# 3__SO-DIMM.net
KiCad netlist of a schematic drawn in Altium Designer
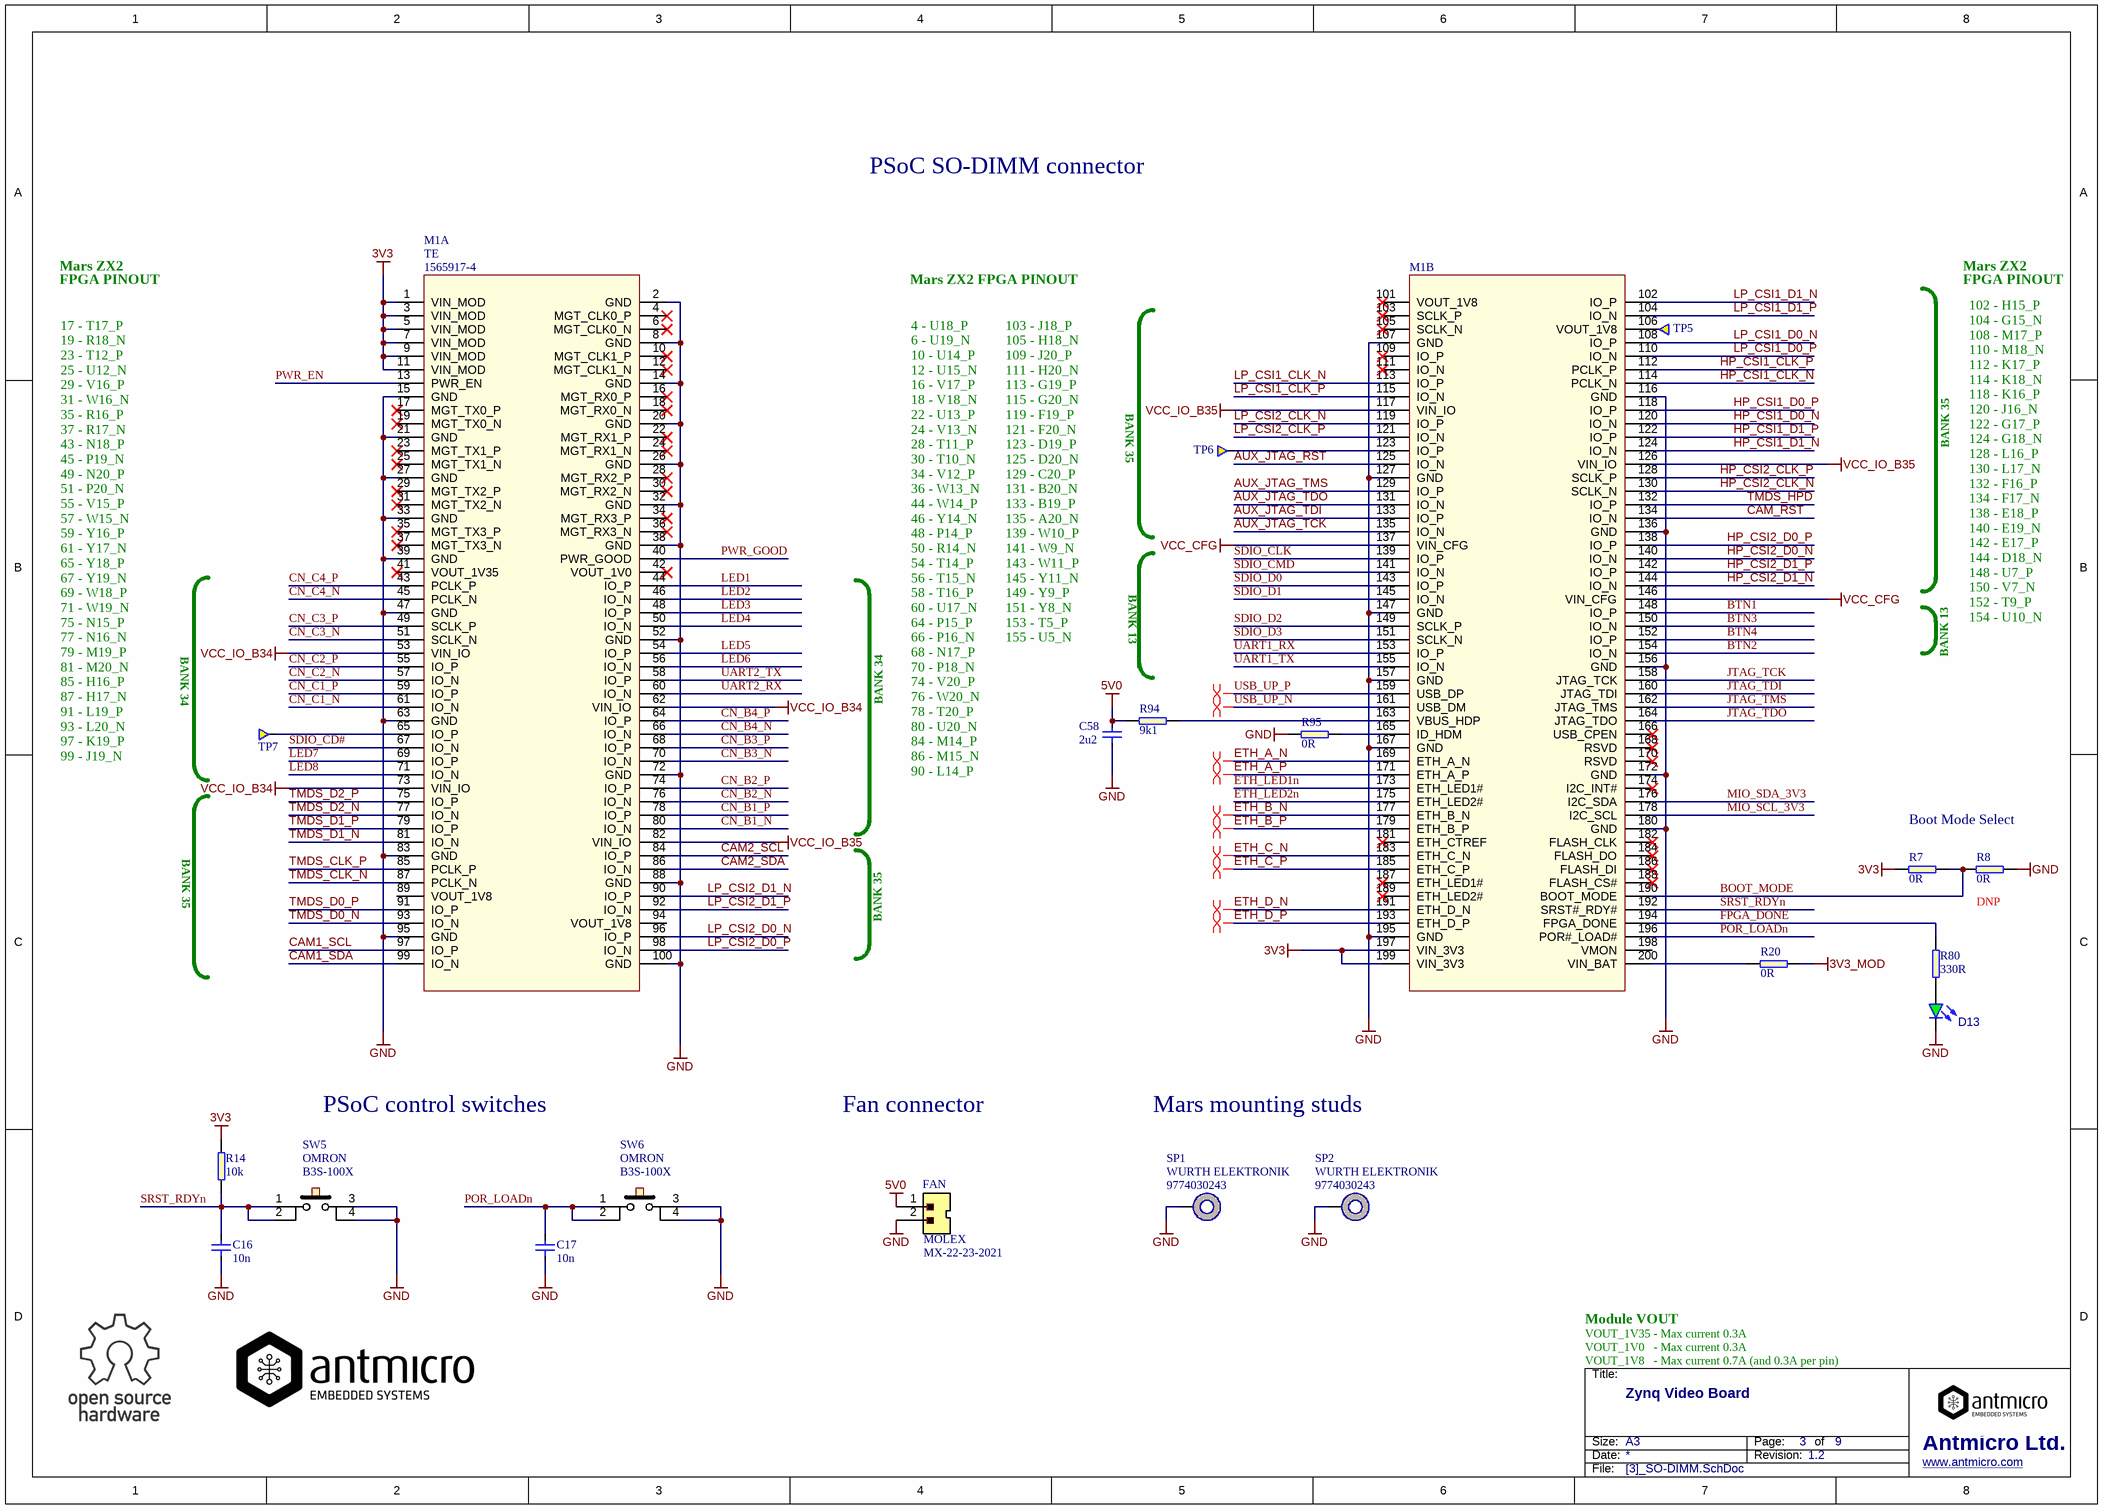
[diagram p0: [3]_SO-DIMM.SchDoc]

(export (version "E")
  (design (tool "Eeschema 10.0.6"))
  (components
    (comp (ref "C16")
      (value "10n")
      (footprint "0402")
      (description "MLCC SMT Capacitor 10nF 0402")
      (fields (field (name "PART NUMBER") "C_10n_0402") (field (name "VOLTAGE") "50V"))
      (libsource (lib "Zynq-Video-Board-Rev-1.2") (part "C_10n_0402"))
    )
    (comp (ref "C17")
      (value "10n")
      (footprint "0402")
      (description "MLCC SMT Capacitor 10nF 0402")
      (fields (field (name "PART NUMBER") "C_10n_0402") (field (name "VOLTAGE") "50V"))
      (libsource (lib "Zynq-Video-Board-Rev-1.2") (part "C_10n_0402"))
    )
    (comp (ref "C58")
      (value "2u2")
      (footprint "0603")
      (description "MLCC SMT Capacitor 2u2F 0603")
      (fields (field (name "PART NUMBER") "C_2u2_0603") (field (name "VOLTAGE") "35V"))
      (libsource (lib "Zynq-Video-Board-Rev-1.2") (part "C_2u2_0603"))
    )
    (comp (ref "D13")
      (value "KPT-1608SGC")
      (footprint "LED0603")
      (description "LED Green 0603 case")
      (fields (field (name "PART NUMBER") "LED_G") (field (name "MANUFACTURER") "KINGBRIGHT"))
      (libsource (lib "Zynq-Video-Board-Rev-1.2") (part "LED"))
    )
    (comp (ref "FAN")
      (value "MX-22-23-2021")
      (footprint "molex_2223-2021")
      (description "Pinhead connector with key")
      (fields (field (name "PART NUMBER") "molex_2223-2021") (field (name "MANUFACTURER") "MOLEX"))
      (libsource (lib "Zynq-Video-Board-Rev-1.2") (part "molex_2223-2021"))
    )
    (comp (ref "M1")
      (value "1565917-4")
      (footprint "TE_1565917-4")
      (description "SODIMM Connector 200_1V8")
      (fields (field (name "PART NUMBER") "Mars ZX2") (field (name "MANUFACTURER") "TE"))
      (libsource (lib "Zynq-Video-Board-Rev-1.2") (part "Mars ZX2"))
    )
    (comp (ref "R7")
      (value "0R")
      (footprint "0402")
      (description "SMT Resistor 0R 0402")
      (fields (field (name "PART NUMBER") "R_0R_0402") (field (name "MANUFACTURER") "MULTICOMP"))
      (libsource (lib "Zynq-Video-Board-Rev-1.2") (part "R_0R_0402"))
    )
    (comp (ref "R8")
      (value "0R")
      (footprint "0402")
      (description "SMT Resistor 0R 0402")
      (fields (field (name "PART NUMBER") "R_0R_0402") (field (name "MANUFACTURER") "MULTICOMP"))
      (libsource (lib "Zynq-Video-Board-Rev-1.2") (part "R_0R_0402"))
    )
    (comp (ref "R14")
      (value "10k")
      (footprint "0402")
      (description "SMT Resistor 10k 0402")
      (fields (field (name "PART NUMBER") "R_10k_0402") (field (name "TOLERANCE") "1%"))
      (libsource (lib "Zynq-Video-Board-Rev-1.2") (part "R_10k_0402"))
    )
    (comp (ref "R20")
      (value "0R")
      (footprint "0402")
      (description "SMT Resistor 0R 0402")
      (fields (field (name "PART NUMBER") "R_0R_0402") (field (name "MANUFACTURER") "MULTICOMP"))
      (libsource (lib "Zynq-Video-Board-Rev-1.2") (part "R_0R_0402"))
    )
    (comp (ref "R80")
      (value "330R")
      (footprint "0402")
      (description "SMT Resistor 330R 0402")
      (fields (field (name "PART NUMBER") "R_330R_0402") (field (name "TOLERANCE") "1%"))
      (libsource (lib "Zynq-Video-Board-Rev-1.2") (part "R_330R_0402"))
    )
    (comp (ref "R94")
      (value "9k1")
      (footprint "0402")
      (description "SMT Resistor 9k1 0402")
      (fields (field (name "PART NUMBER") "R_9k1_0402") (field (name "TOLERANCE") "1%"))
      (libsource (lib "Zynq-Video-Board-Rev-1.2") (part "R_9k1_0402"))
    )
    (comp (ref "R95")
      (value "0R")
      (footprint "0402")
      (description "SMT Resistor 0R 0402")
      (fields (field (name "PART NUMBER") "R_0R_0402") (field (name "MANUFACTURER") "MULTICOMP"))
      (libsource (lib "Zynq-Video-Board-Rev-1.2") (part "R_0R_0402"))
    )
    (comp (ref "SP1")
      (value "9774030243")
      (footprint "M2-3mm")
      (description "M2x3")
      (fields (field (name "PART NUMBER") "WE_9774030243") (field (name "MANUFACTURER") "WURTH ELEKTRONIK"))
      (libsource (lib "Zynq-Video-Board-Rev-1.2") (part "SPACER"))
    )
    (comp (ref "SP2")
      (value "9774030243")
      (footprint "M2-3mm")
      (description "M2x3")
      (fields (field (name "PART NUMBER") "WE_9774030243") (field (name "MANUFACTURER") "WURTH ELEKTRONIK"))
      (libsource (lib "Zynq-Video-Board-Rev-1.2") (part "SPACER"))
    )
    (comp (ref "SW5")
      (value "B3S-100X")
      (footprint "B3S-100X")
      (description "Tactile switch")
      (fields (field (name "PART NUMBER") "B3S-1002") (field (name "MANUFACTURER") "OMRON"))
      (libsource (lib "Zynq-Video-Board-Rev-1.2") (part "TACTILE_SWITCH"))
    )
    (comp (ref "SW6")
      (value "B3S-100X")
      (footprint "B3S-100X")
      (description "Tactile switch")
      (fields (field (name "PART NUMBER") "B3S-1002") (field (name "MANUFACTURER") "OMRON"))
      (libsource (lib "Zynq-Video-Board-Rev-1.2") (part "TACTILE_SWITCH"))
    )
    (comp (ref "TP5")
      (value "Testpad")
      (footprint "TP-R-2")
      (description "Testpad, round, 2mm")
      (fields (field (name "PART NUMBER") "TP-R-2"))
      (libsource (lib "Zynq-Video-Board-Rev-1.2") (part "Testpad"))
    )
    (comp (ref "TP6")
      (value "Testpad")
      (footprint "TP-R-2")
      (description "Testpad, round, 2mm")
      (fields (field (name "PART NUMBER") "TP-R-2"))
      (libsource (lib "Zynq-Video-Board-Rev-1.2") (part "Testpad"))
    )
    (comp (ref "TP7")
      (value "Testpad")
      (footprint "TP-R-2")
      (description "Testpad, round, 2mm")
      (fields (field (name "PART NUMBER") "TP-R-2"))
      (libsource (lib "Zynq-Video-Board-Rev-1.2") (part "Testpad"))
    )
  )
  (nets
    (net (code "1") (name "/AUX_JTAG_RST") (class "Default")
      (node (ref "M1") (pin "125") (pinfunction "IO_N_125") (pintype "passive"))
    )
    (net (code "2") (name "/AUX_JTAG_TCK") (class "Default")
      (node (ref "M1") (pin "135") (pinfunction "IO_N_135") (pintype "passive"))
    )
    (net (code "3") (name "/AUX_JTAG_TDI") (class "Default")
      (node (ref "M1") (pin "133") (pinfunction "IO_P_133") (pintype "passive"))
    )
    (net (code "4") (name "/AUX_JTAG_TDO") (class "Default")
      (node (ref "M1") (pin "131") (pinfunction "IO_N_131") (pintype "passive"))
    )
    (net (code "5") (name "/AUX_JTAG_TMS") (class "Default")
      (node (ref "M1") (pin "129") (pinfunction "IO_P_129") (pintype "passive"))
    )
    (net (code "6") (name "/BOOT_MODE") (class "Default")
      (node (ref "M1") (pin "190") (pinfunction "BOOT_MODE_190") (pintype "passive"))
      (node (ref "R7") (pin "2") (pintype "passive"))
      (node (ref "R8") (pin "1") (pintype "passive"))
    )
    (net (code "7") (name "/BTN1") (class "Default")
      (node (ref "M1") (pin "148") (pinfunction "IO_P_148") (pintype "passive"))
    )
    (net (code "8") (name "/BTN2") (class "Default")
      (node (ref "M1") (pin "154") (pinfunction "IO_N_154") (pintype "passive"))
    )
    (net (code "9") (name "/BTN3") (class "Default")
      (node (ref "M1") (pin "150") (pinfunction "IO_N_150") (pintype "passive"))
    )
    (net (code "10") (name "/BTN4") (class "Default")
      (node (ref "M1") (pin "152") (pinfunction "IO_P_152") (pintype "passive"))
    )
    (net (code "11") (name "/CAM1_SCL") (class "Default")
      (node (ref "M1") (pin "97") (pinfunction "IO_P_97") (pintype "passive"))
    )
    (net (code "12") (name "/CAM1_SDA") (class "Default")
      (node (ref "M1") (pin "99") (pinfunction "IO_N_99") (pintype "passive"))
    )
    (net (code "13") (name "/CAM2_SCL") (class "Default")
      (node (ref "M1") (pin "84") (pinfunction "IO_P_84") (pintype "passive"))
    )
    (net (code "14") (name "/CAM2_SDA") (class "Default")
      (node (ref "M1") (pin "86") (pinfunction "IO_N_86") (pintype "passive"))
    )
    (net (code "15") (name "/CAM_RST") (class "Default")
      (node (ref "M1") (pin "134") (pinfunction "IO_N_134") (pintype "passive"))
    )
    (net (code "16") (name "/CN_B1_N") (class "Default")
      (node (ref "M1") (pin "80") (pinfunction "IO_N_80") (pintype "passive"))
    )
    (net (code "17") (name "/CN_B1_P") (class "Default")
      (node (ref "M1") (pin "78") (pinfunction "IO_P_78") (pintype "passive"))
    )
    (net (code "18") (name "/CN_B2_N") (class "Default")
      (node (ref "M1") (pin "76") (pinfunction "IO_N_76") (pintype "passive"))
    )
    (net (code "19") (name "/CN_B2_P") (class "Default")
      (node (ref "M1") (pin "74") (pinfunction "IO_P_74") (pintype "passive"))
    )
    (net (code "20") (name "/CN_B3_N") (class "Default")
      (node (ref "M1") (pin "70") (pinfunction "IO_N_70") (pintype "passive"))
    )
    (net (code "21") (name "/CN_B3_P") (class "Default")
      (node (ref "M1") (pin "68") (pinfunction "IO_P_68") (pintype "passive"))
    )
    (net (code "22") (name "/CN_B4_N") (class "Default")
      (node (ref "M1") (pin "66") (pinfunction "IO_N_66") (pintype "passive"))
    )
    (net (code "23") (name "/CN_B4_P") (class "Default")
      (node (ref "M1") (pin "64") (pinfunction "IO_P_64") (pintype "passive"))
    )
    (net (code "24") (name "/CN_C1_N") (class "Default")
      (node (ref "M1") (pin "61") (pinfunction "IO_N_61") (pintype "passive"))
    )
    (net (code "25") (name "/CN_C1_P") (class "Default")
      (node (ref "M1") (pin "59") (pinfunction "IO_P_59") (pintype "passive"))
    )
    (net (code "26") (name "/CN_C2_N") (class "Default")
      (node (ref "M1") (pin "57") (pinfunction "IO_N_57") (pintype "passive"))
    )
    (net (code "27") (name "/CN_C2_P") (class "Default")
      (node (ref "M1") (pin "55") (pinfunction "IO_P_55") (pintype "passive"))
    )
    (net (code "28") (name "/CN_C3_N") (class "Default")
      (node (ref "M1") (pin "51") (pinfunction "SCLK_N_51") (pintype "passive"))
    )
    (net (code "29") (name "/CN_C3_P") (class "Default")
      (node (ref "M1") (pin "49") (pinfunction "SCLK_P_49") (pintype "passive"))
    )
    (net (code "30") (name "/CN_C4_N") (class "Default")
      (node (ref "M1") (pin "45") (pinfunction "PCLK_N_45") (pintype "passive"))
    )
    (net (code "31") (name "/CN_C4_P") (class "Default")
      (node (ref "M1") (pin "43") (pinfunction "PCLK_P_43") (pintype "passive"))
    )
    (net (code "32") (name "/ETH_A_N") (class "Default")
      (node (ref "M1") (pin "169") (pinfunction "ETH_A_N_169") (pintype "passive"))
    )
    (net (code "33") (name "/ETH_A_P") (class "Default")
      (node (ref "M1") (pin "171") (pinfunction "ETH_A_P_171") (pintype "passive"))
    )
    (net (code "34") (name "/ETH_B_N") (class "Default")
      (node (ref "M1") (pin "177") (pinfunction "ETH_B_N_177") (pintype "passive"))
    )
    (net (code "35") (name "/ETH_B_P") (class "Default")
      (node (ref "M1") (pin "179") (pinfunction "ETH_B_P_179") (pintype "passive"))
    )
    (net (code "36") (name "/ETH_C_N") (class "Default")
      (node (ref "M1") (pin "183") (pinfunction "ETH_C_N_183") (pintype "passive"))
    )
    (net (code "37") (name "/ETH_C_P") (class "Default")
      (node (ref "M1") (pin "185") (pinfunction "ETH_C_P_185") (pintype "passive"))
    )
    (net (code "38") (name "/ETH_D_N") (class "Default")
      (node (ref "M1") (pin "191") (pinfunction "ETH_D_N_191") (pintype "passive"))
    )
    (net (code "39") (name "/ETH_D_P") (class "Default")
      (node (ref "M1") (pin "193") (pinfunction "ETH_D_P_193") (pintype "passive"))
    )
    (net (code "40") (name "/ETH_LED1n") (class "Default")
      (node (ref "M1") (pin "173") (pinfunction "ETH_LED1#_173") (pintype "passive"))
    )
    (net (code "41") (name "/ETH_LED2n") (class "Default")
      (node (ref "M1") (pin "175") (pinfunction "ETH_LED2#_175") (pintype "passive"))
    )
    (net (code "42") (name "/FPGA_DONE") (class "Default")
      (node (ref "M1") (pin "194") (pinfunction "FPGA_DONE_194") (pintype "passive"))
      (node (ref "R80") (pin "2") (pintype "passive"))
    )
    (net (code "43") (name "/HP_CSI1_CLK_N") (class "Default")
      (node (ref "M1") (pin "114") (pinfunction "PCLK_N_114") (pintype "passive"))
    )
    (net (code "44") (name "/HP_CSI1_CLK_P") (class "Default")
      (node (ref "M1") (pin "112") (pinfunction "PCLK_P_112") (pintype "passive"))
    )
    (net (code "45") (name "/HP_CSI1_D0_N") (class "Default")
      (node (ref "M1") (pin "120") (pinfunction "IO_N_120") (pintype "passive"))
    )
    (net (code "46") (name "/HP_CSI1_D0_P") (class "Default")
      (node (ref "M1") (pin "118") (pinfunction "IO_P_118") (pintype "passive"))
    )
    (net (code "47") (name "/HP_CSI1_D1_N") (class "Default")
      (node (ref "M1") (pin "124") (pinfunction "IO_N_124") (pintype "passive"))
    )
    (net (code "48") (name "/HP_CSI1_D1_P") (class "Default")
      (node (ref "M1") (pin "122") (pinfunction "IO_P_122") (pintype "passive"))
    )
    (net (code "49") (name "/HP_CSI2_CLK_N") (class "Default")
      (node (ref "M1") (pin "130") (pinfunction "SCLK_N_130") (pintype "passive"))
    )
    (net (code "50") (name "/HP_CSI2_CLK_P") (class "Default")
      (node (ref "M1") (pin "128") (pinfunction "SCLK_P_128") (pintype "passive"))
    )
    (net (code "51") (name "/HP_CSI2_D0_N") (class "Default")
      (node (ref "M1") (pin "140") (pinfunction "IO_N_140") (pintype "passive"))
    )
    (net (code "52") (name "/HP_CSI2_D0_P") (class "Default")
      (node (ref "M1") (pin "138") (pinfunction "IO_P_138") (pintype "passive"))
    )
    (net (code "53") (name "/HP_CSI2_D1_N") (class "Default")
      (node (ref "M1") (pin "144") (pinfunction "IO_N_144") (pintype "passive"))
    )
    (net (code "54") (name "/HP_CSI2_D1_P") (class "Default")
      (node (ref "M1") (pin "142") (pinfunction "IO_P_142") (pintype "passive"))
    )
    (net (code "55") (name "/JTAG_TCK") (class "Default")
      (node (ref "M1") (pin "158") (pinfunction "JTAG_TCK_158") (pintype "passive"))
    )
    (net (code "56") (name "/JTAG_TDI") (class "Default")
      (node (ref "M1") (pin "160") (pinfunction "JTAG_TDI_160") (pintype "passive"))
    )
    (net (code "57") (name "/JTAG_TDO") (class "Default")
      (node (ref "M1") (pin "164") (pinfunction "JTAG_TDO_164") (pintype "passive"))
    )
    (net (code "58") (name "/JTAG_TMS") (class "Default")
      (node (ref "M1") (pin "162") (pinfunction "JTAG_TMS_162") (pintype "passive"))
    )
    (net (code "59") (name "/LED1") (class "Default")
      (node (ref "M1") (pin "44") (pinfunction "IO_P_44") (pintype "passive"))
    )
    (net (code "60") (name "/LED2") (class "Default")
      (node (ref "M1") (pin "46") (pinfunction "IO_N_46") (pintype "passive"))
    )
    (net (code "61") (name "/LED3") (class "Default")
      (node (ref "M1") (pin "48") (pinfunction "IO_P_48") (pintype "passive"))
    )
    (net (code "62") (name "/LED4") (class "Default")
      (node (ref "M1") (pin "50") (pinfunction "IO_N_50") (pintype "passive"))
    )
    (net (code "63") (name "/LED5") (class "Default")
      (node (ref "M1") (pin "54") (pinfunction "IO_P_54") (pintype "passive"))
    )
    (net (code "64") (name "/LED6") (class "Default")
      (node (ref "M1") (pin "56") (pinfunction "IO_N_56") (pintype "passive"))
    )
    (net (code "65") (name "/LED7") (class "Default")
      (node (ref "M1") (pin "69") (pinfunction "IO_P_69") (pintype "passive"))
    )
    (net (code "66") (name "/LED8") (class "Default")
      (node (ref "M1") (pin "71") (pinfunction "IO_N_71") (pintype "passive"))
    )
    (net (code "67") (name "/LP_CSI1_CLK_N") (class "Default")
      (node (ref "M1") (pin "113") (pinfunction "IO_P_113") (pintype "passive"))
    )
    (net (code "68") (name "/LP_CSI1_CLK_P") (class "Default")
      (node (ref "M1") (pin "115") (pinfunction "IO_N_115") (pintype "passive"))
    )
    (net (code "69") (name "/LP_CSI1_D0_N") (class "Default")
      (node (ref "M1") (pin "108") (pinfunction "IO_P_108") (pintype "passive"))
    )
    (net (code "70") (name "/LP_CSI1_D0_P") (class "Default")
      (node (ref "M1") (pin "110") (pinfunction "IO_N_110") (pintype "passive"))
    )
    (net (code "71") (name "/LP_CSI1_D1_N") (class "Default")
      (node (ref "M1") (pin "102") (pinfunction "IO_P_102") (pintype "passive"))
    )
    (net (code "72") (name "/LP_CSI1_D1_P") (class "Default")
      (node (ref "M1") (pin "104") (pinfunction "IO_N_104") (pintype "passive"))
    )
    (net (code "73") (name "/LP_CSI2_CLK_N") (class "Default")
      (node (ref "M1") (pin "119") (pinfunction "IO_P_119") (pintype "passive"))
    )
    (net (code "74") (name "/LP_CSI2_CLK_P") (class "Default")
      (node (ref "M1") (pin "121") (pinfunction "IO_N_121") (pintype "passive"))
    )
    (net (code "75") (name "/LP_CSI2_D0_N") (class "Default")
      (node (ref "M1") (pin "96") (pinfunction "IO_P_96") (pintype "passive"))
    )
    (net (code "76") (name "/LP_CSI2_D0_P") (class "Default")
      (node (ref "M1") (pin "98") (pinfunction "IO_N_98") (pintype "passive"))
    )
    (net (code "77") (name "/LP_CSI2_D1_N") (class "Default")
      (node (ref "M1") (pin "90") (pinfunction "IO_P_90") (pintype "passive"))
    )
    (net (code "78") (name "/LP_CSI2_D1_P") (class "Default")
      (node (ref "M1") (pin "92") (pinfunction "IO_N_92") (pintype "passive"))
    )
    (net (code "79") (name "/MIO_SCL_3V3") (class "Default")
      (node (ref "M1") (pin "178") (pinfunction "I2C_SCL_178") (pintype "passive"))
    )
    (net (code "80") (name "/MIO_SDA_3V3") (class "Default")
      (node (ref "M1") (pin "176") (pinfunction "I2C_SDA_176") (pintype "passive"))
    )
    (net (code "81") (name "/POR_LOADn") (class "Default")
      (node (ref "C17") (pin "2") (pinfunction "2_2") (pintype "passive"))
      (node (ref "M1") (pin "196") (pinfunction "POR#_LOAD#_196") (pintype "passive"))
      (node (ref "SW6") (pin "1") (pinfunction "1_1") (pintype "passive"))
      (node (ref "SW6") (pin "2") (pinfunction "2_2") (pintype "passive"))
    )
    (net (code "82") (name "/PWR_EN") (class "Default")
      (node (ref "M1") (pin "13") (pinfunction "PWR_EN_13") (pintype "passive"))
    )
    (net (code "83") (name "/PWR_GOOD") (class "Default")
      (node (ref "M1") (pin "40") (pinfunction "PWR_GOOD_40") (pintype "passive"))
    )
    (net (code "84") (name "/SDIO_CD#") (class "Default")
      (node (ref "M1") (pin "67") (pinfunction "IO_N_67") (pintype "passive"))
    )
    (net (code "85") (name "/SDIO_CLK") (class "Default")
      (node (ref "M1") (pin "139") (pinfunction "IO_P_139") (pintype "passive"))
    )
    (net (code "86") (name "/SDIO_CMD") (class "Default")
      (node (ref "M1") (pin "141") (pinfunction "IO_N_141") (pintype "passive"))
    )
    (net (code "87") (name "/SDIO_D0") (class "Default")
      (node (ref "M1") (pin "143") (pinfunction "IO_P_143") (pintype "passive"))
    )
    (net (code "88") (name "/SDIO_D1") (class "Default")
      (node (ref "M1") (pin "145") (pinfunction "IO_N_145") (pintype "passive"))
    )
    (net (code "89") (name "/SDIO_D2") (class "Default")
      (node (ref "M1") (pin "149") (pinfunction "SCLK_P_149") (pintype "passive"))
    )
    (net (code "90") (name "/SDIO_D3") (class "Default")
      (node (ref "M1") (pin "151") (pinfunction "SCLK_N_151") (pintype "passive"))
    )
    (net (code "91") (name "/SRST_RDYn") (class "Default")
      (node (ref "C16") (pin "2") (pinfunction "2_2") (pintype "passive"))
      (node (ref "M1") (pin "192") (pinfunction "SRST#_RDY#_192") (pintype "passive"))
      (node (ref "R14") (pin "2") (pintype "passive"))
      (node (ref "SW5") (pin "1") (pinfunction "1_1") (pintype "passive"))
      (node (ref "SW5") (pin "2") (pinfunction "2_2") (pintype "passive"))
    )
    (net (code "92") (name "/TMDS_CLK_N") (class "Default")
      (node (ref "M1") (pin "87") (pinfunction "PCLK_N_87") (pintype "passive"))
    )
    (net (code "93") (name "/TMDS_CLK_P") (class "Default")
      (node (ref "M1") (pin "85") (pinfunction "PCLK_P_85") (pintype "passive"))
    )
    (net (code "94") (name "/TMDS_D0_N") (class "Default")
      (node (ref "M1") (pin "93") (pinfunction "IO_N_93") (pintype "passive"))
    )
    (net (code "95") (name "/TMDS_D0_P") (class "Default")
      (node (ref "M1") (pin "91") (pinfunction "IO_P_91") (pintype "passive"))
    )
    (net (code "96") (name "/TMDS_D1_N") (class "Default")
      (node (ref "M1") (pin "81") (pinfunction "IO_N_81") (pintype "passive"))
    )
    (net (code "97") (name "/TMDS_D1_P") (class "Default")
      (node (ref "M1") (pin "79") (pinfunction "IO_P_79") (pintype "passive"))
    )
    (net (code "98") (name "/TMDS_D2_N") (class "Default")
      (node (ref "M1") (pin "77") (pinfunction "IO_N_77") (pintype "passive"))
    )
    (net (code "99") (name "/TMDS_D2_P") (class "Default")
      (node (ref "M1") (pin "75") (pinfunction "IO_P_75") (pintype "passive"))
    )
    (net (code "100") (name "/TMDS_HPD") (class "Default")
      (node (ref "M1") (pin "132") (pinfunction "IO_P_132") (pintype "passive"))
    )
    (net (code "101") (name "/UART1_RX") (class "Default")
      (node (ref "M1") (pin "153") (pinfunction "IO_P_153") (pintype "passive"))
    )
    (net (code "102") (name "/UART1_TX") (class "Default")
      (node (ref "M1") (pin "155") (pinfunction "IO_N_155") (pintype "passive"))
    )
    (net (code "103") (name "/UART2_RX") (class "Default")
      (node (ref "M1") (pin "60") (pinfunction "IO_N_60") (pintype "passive"))
    )
    (net (code "104") (name "/UART2_TX") (class "Default")
      (node (ref "M1") (pin "58") (pinfunction "IO_P_58") (pintype "passive"))
    )
    (net (code "105") (name "/USB_UP_N") (class "Default")
      (node (ref "M1") (pin "161") (pinfunction "USB_DM_161") (pintype "passive"))
    )
    (net (code "106") (name "/USB_UP_P") (class "Default")
      (node (ref "M1") (pin "159") (pinfunction "USB_DP_159") (pintype "passive"))
    )
    (net (code "107") (name "3V3") (class "Default")
      (node (ref "M1") (pin "1") (pinfunction "VIN_MOD_1") (pintype "passive"))
      (node (ref "M1") (pin "11") (pinfunction "VIN_MOD_11") (pintype "passive"))
      (node (ref "M1") (pin "197") (pinfunction "VIN_3V3_197") (pintype "passive"))
      (node (ref "M1") (pin "199") (pinfunction "VIN_3V3_199") (pintype "passive"))
      (node (ref "M1") (pin "3") (pinfunction "VIN_MOD_3") (pintype "passive"))
      (node (ref "M1") (pin "5") (pinfunction "VIN_MOD_5") (pintype "passive"))
      (node (ref "M1") (pin "7") (pinfunction "VIN_MOD_7") (pintype "passive"))
      (node (ref "M1") (pin "9") (pinfunction "VIN_MOD_9") (pintype "passive"))
      (node (ref "R14") (pin "1") (pintype "passive"))
      (node (ref "R7") (pin "1") (pintype "passive"))
    )
    (net (code "108") (name "3V3_MOD") (class "Default") (node (ref "R20") (pin "2") (pintype "passive")))
    (net (code "109") (name "5V0") (class "Default")
      (node (ref "C58") (pin "2") (pinfunction "2_2") (pintype "passive"))
      (node (ref "FAN") (pin "1") (pinfunction "1_1") (pintype "passive"))
      (node (ref "R94") (pin "1") (pintype "passive"))
    )
    (net (code "110") (name "GND") (class "Default")
      (node (ref "C16") (pin "1") (pinfunction "1_1") (pintype "passive"))
      (node (ref "C17") (pin "1") (pinfunction "1_1") (pintype "passive"))
      (node (ref "C58") (pin "1") (pinfunction "1_1") (pintype "passive"))
      (node (ref "D13") (pin "K") (pinfunction "K_K") (pintype "passive"))
      (node (ref "FAN") (pin "2") (pinfunction "2_2") (pintype "passive"))
      (node (ref "M1") (pin "100") (pinfunction "GND_100") (pintype "passive"))
      (node (ref "M1") (pin "107") (pinfunction "GND_107") (pintype "passive"))
      (node (ref "M1") (pin "116") (pinfunction "GND_116") (pintype "passive"))
      (node (ref "M1") (pin "127") (pinfunction "GND_127") (pintype "passive"))
      (node (ref "M1") (pin "136") (pinfunction "GND_136") (pintype "passive"))
      (node (ref "M1") (pin "14") (pinfunction "GND_14") (pintype "passive"))
      (node (ref "M1") (pin "147") (pinfunction "GND_147") (pintype "passive"))
      (node (ref "M1") (pin "15") (pinfunction "GND_15") (pintype "passive"))
      (node (ref "M1") (pin "156") (pinfunction "GND_156") (pintype "passive"))
      (node (ref "M1") (pin "157") (pinfunction "GND_157") (pintype "passive"))
      (node (ref "M1") (pin "167") (pinfunction "GND_167") (pintype "passive"))
      (node (ref "M1") (pin "172") (pinfunction "GND_172") (pintype "passive"))
      (node (ref "M1") (pin "180") (pinfunction "GND_180") (pintype "passive"))
      (node (ref "M1") (pin "195") (pinfunction "GND_195") (pintype "passive"))
      (node (ref "M1") (pin "2") (pinfunction "GND_2") (pintype "passive"))
      (node (ref "M1") (pin "20") (pinfunction "GND_20") (pintype "passive"))
      (node (ref "M1") (pin "21") (pinfunction "GND_21") (pintype "passive"))
      (node (ref "M1") (pin "26") (pinfunction "GND_26") (pintype "passive"))
      (node (ref "M1") (pin "27") (pinfunction "GND_27") (pintype "passive"))
      (node (ref "M1") (pin "32") (pinfunction "GND_32") (pintype "passive"))
      (node (ref "M1") (pin "33") (pinfunction "GND_33") (pintype "passive"))
      (node (ref "M1") (pin "38") (pinfunction "GND_38") (pintype "passive"))
      (node (ref "M1") (pin "39") (pinfunction "GND_39") (pintype "passive"))
      (node (ref "M1") (pin "47") (pinfunction "GND_47") (pintype "passive"))
      (node (ref "M1") (pin "52") (pinfunction "GND_52") (pintype "passive"))
      (node (ref "M1") (pin "63") (pinfunction "GND_63") (pintype "passive"))
      (node (ref "M1") (pin "72") (pinfunction "GND_72") (pintype "passive"))
      (node (ref "M1") (pin "8") (pinfunction "GND_8") (pintype "passive"))
      (node (ref "M1") (pin "83") (pinfunction "GND_83") (pintype "passive"))
      (node (ref "M1") (pin "88") (pinfunction "GND_88") (pintype "passive"))
      (node (ref "M1") (pin "95") (pinfunction "GND_95") (pintype "passive"))
      (node (ref "R8") (pin "2") (pintype "passive"))
      (node (ref "R95") (pin "1") (pintype "passive"))
      (node (ref "SP1") (pin "1") (pinfunction "1_1") (pintype "passive"))
      (node (ref "SP2") (pin "1") (pinfunction "1_1") (pintype "passive"))
      (node (ref "SW5") (pin "3") (pinfunction "3_3") (pintype "passive"))
      (node (ref "SW5") (pin "4") (pinfunction "4_4") (pintype "passive"))
      (node (ref "SW6") (pin "3") (pinfunction "3_3") (pintype "passive"))
      (node (ref "SW6") (pin "4") (pinfunction "4_4") (pintype "passive"))
    )
    (net (code "111") (name "Net-(D13-PadA)") (class "Default")
      (node (ref "D13") (pin "A") (pinfunction "A_A") (pintype "passive"))
      (node (ref "R80") (pin "1") (pintype "passive"))
    )
    (net (code "112") (name "Net-(M1A-IO_P-Pad65)") (class "Default")
      (node (ref "M1") (pin "65") (pinfunction "IO_P_65") (pintype "passive"))
      (node (ref "TP7") (pin "1") (pintype "passive"))
    )
    (net (code "113") (name "Net-(M1B-ID_HDM)") (class "Default")
      (node (ref "M1") (pin "165") (pinfunction "ID_HDM_165") (pintype "passive"))
      (node (ref "R95") (pin "2") (pintype "passive"))
    )
    (net (code "114") (name "Net-(M1B-IO_P-Pad123)") (class "Default")
      (node (ref "M1") (pin "123") (pinfunction "IO_P_123") (pintype "passive"))
      (node (ref "TP6") (pin "1") (pintype "passive"))
    )
    (net (code "115") (name "Net-(M1B-VBUS_HDP)") (class "Default")
      (node (ref "M1") (pin "163") (pinfunction "VBUS_HDP_163") (pintype "passive"))
      (node (ref "R94") (pin "2") (pintype "passive"))
    )
    (net (code "116") (name "Net-(M1B-VIN_BAT)") (class "Default")
      (node (ref "M1") (pin "200") (pinfunction "VIN_BAT_200") (pintype "passive"))
      (node (ref "R20") (pin "1") (pintype "passive"))
    )
    (net (code "117") (name "Net-(M1B-VOUT_1V8-Pad106)") (class "Default")
      (node (ref "M1") (pin "106") (pinfunction "VOUT_1V8_106") (pintype "passive"))
      (node (ref "TP5") (pin "1") (pintype "passive"))
    )
    (net (code "118") (name "VCC_CFG") (class "Default")
      (node (ref "M1") (pin "137") (pinfunction "VIN_CFG_137") (pintype "passive"))
      (node (ref "M1") (pin "146") (pinfunction "VIN_CFG_146") (pintype "passive"))
    )
    (net (code "119") (name "VCC_IO_B34") (class "Default")
      (node (ref "M1") (pin "53") (pinfunction "VIN_IO_53") (pintype "passive"))
      (node (ref "M1") (pin "62") (pinfunction "VIN_IO_62") (pintype "passive"))
      (node (ref "M1") (pin "73") (pinfunction "VIN_IO_73") (pintype "passive"))
    )
    (net (code "120") (name "VCC_IO_B35") (class "Default")
      (node (ref "M1") (pin "117") (pinfunction "VIN_IO_117") (pintype "passive"))
      (node (ref "M1") (pin "126") (pinfunction "VIN_IO_126") (pintype "passive"))
      (node (ref "M1") (pin "82") (pinfunction "VIN_IO_82") (pintype "passive"))
    )
    (net (code "121") (name "unconnected-(M1A-MGT_CLK0_N-Pad6)") (class "Default")
      (node (ref "M1") (pin "6") (pinfunction "MGT_CLK0_N_6") (pintype "passive+no_connect"))
    )
    (net (code "122") (name "unconnected-(M1A-MGT_CLK0_P-Pad4)") (class "Default")
      (node (ref "M1") (pin "4") (pinfunction "MGT_CLK0_P_4") (pintype "passive+no_connect"))
    )
    (net (code "123") (name "unconnected-(M1A-MGT_CLK1_N-Pad12)") (class "Default")
      (node (ref "M1") (pin "12") (pinfunction "MGT_CLK1_N_12") (pintype "passive+no_connect"))
    )
    (net (code "124") (name "unconnected-(M1A-MGT_CLK1_P-Pad10)") (class "Default")
      (node (ref "M1") (pin "10") (pinfunction "MGT_CLK1_P_10") (pintype "passive+no_connect"))
    )
    (net (code "125") (name "unconnected-(M1A-MGT_RX0_N-Pad18)") (class "Default")
      (node (ref "M1") (pin "18") (pinfunction "MGT_RX0_N_18") (pintype "passive+no_connect"))
    )
    (net (code "126") (name "unconnected-(M1A-MGT_RX0_P-Pad16)") (class "Default")
      (node (ref "M1") (pin "16") (pinfunction "MGT_RX0_P_16") (pintype "passive+no_connect"))
    )
    (net (code "127") (name "unconnected-(M1A-MGT_RX1_N-Pad24)") (class "Default")
      (node (ref "M1") (pin "24") (pinfunction "MGT_RX1_N_24") (pintype "passive+no_connect"))
    )
    (net (code "128") (name "unconnected-(M1A-MGT_RX1_P-Pad22)") (class "Default")
      (node (ref "M1") (pin "22") (pinfunction "MGT_RX1_P_22") (pintype "passive+no_connect"))
    )
    (net (code "129") (name "unconnected-(M1A-MGT_RX2_N-Pad30)") (class "Default")
      (node (ref "M1") (pin "30") (pinfunction "MGT_RX2_N_30") (pintype "passive+no_connect"))
    )
    (net (code "130") (name "unconnected-(M1A-MGT_RX2_P-Pad28)") (class "Default")
      (node (ref "M1") (pin "28") (pinfunction "MGT_RX2_P_28") (pintype "passive+no_connect"))
    )
    (net (code "131") (name "unconnected-(M1A-MGT_RX3_N-Pad36)") (class "Default")
      (node (ref "M1") (pin "36") (pinfunction "MGT_RX3_N_36") (pintype "passive+no_connect"))
    )
    (net (code "132") (name "unconnected-(M1A-MGT_RX3_P-Pad34)") (class "Default")
      (node (ref "M1") (pin "34") (pinfunction "MGT_RX3_P_34") (pintype "passive+no_connect"))
    )
    (net (code "133") (name "unconnected-(M1A-MGT_TX0_N-Pad19)") (class "Default")
      (node (ref "M1") (pin "19") (pinfunction "MGT_TX0_N_19") (pintype "passive+no_connect"))
    )
    (net (code "134") (name "unconnected-(M1A-MGT_TX0_P-Pad17)") (class "Default")
      (node (ref "M1") (pin "17") (pinfunction "MGT_TX0_P_17") (pintype "passive+no_connect"))
    )
    (net (code "135") (name "unconnected-(M1A-MGT_TX1_N-Pad25)") (class "Default")
      (node (ref "M1") (pin "25") (pinfunction "MGT_TX1_N_25") (pintype "passive+no_connect"))
    )
    (net (code "136") (name "unconnected-(M1A-MGT_TX1_P-Pad23)") (class "Default")
      (node (ref "M1") (pin "23") (pinfunction "MGT_TX1_P_23") (pintype "passive+no_connect"))
    )
    (net (code "137") (name "unconnected-(M1A-MGT_TX2_N-Pad31)") (class "Default")
      (node (ref "M1") (pin "31") (pinfunction "MGT_TX2_N_31") (pintype "passive+no_connect"))
    )
    (net (code "138") (name "unconnected-(M1A-MGT_TX2_P-Pad29)") (class "Default")
      (node (ref "M1") (pin "29") (pinfunction "MGT_TX2_P_29") (pintype "passive+no_connect"))
    )
    (net (code "139") (name "unconnected-(M1A-MGT_TX3_N-Pad37)") (class "Default")
      (node (ref "M1") (pin "37") (pinfunction "MGT_TX3_N_37") (pintype "passive+no_connect"))
    )
    (net (code "140") (name "unconnected-(M1A-MGT_TX3_P-Pad35)") (class "Default")
      (node (ref "M1") (pin "35") (pinfunction "MGT_TX3_P_35") (pintype "passive+no_connect"))
    )
    (net (code "141") (name "unconnected-(M1A-VOUT_1V0-Pad42)") (class "Default")
      (node (ref "M1") (pin "42") (pinfunction "VOUT_1V0_42") (pintype "passive+no_connect"))
    )
    (net (code "142") (name "unconnected-(M1A-VOUT_1V8-Pad89)") (class "Default")
      (node (ref "M1") (pin "89") (pinfunction "VOUT_1V8_89") (pintype "passive"))
    )
    (net (code "143") (name "unconnected-(M1A-VOUT_1V8-Pad94)") (class "Default")
      (node (ref "M1") (pin "94") (pinfunction "VOUT_1V8_94") (pintype "passive"))
    )
    (net (code "144") (name "unconnected-(M1A-VOUT_1V35-Pad41)") (class "Default")
      (node (ref "M1") (pin "41") (pinfunction "VOUT_1V35_41") (pintype "passive+no_connect"))
    )
    (net (code "145") (name "unconnected-(M1B-ETH_CTREF-Pad181)") (class "Default")
      (node (ref "M1") (pin "181") (pinfunction "ETH_CTREF_181") (pintype "passive+no_connect"))
    )
    (net (code "146") (name "unconnected-(M1B-ETH_LED1#-Pad187)") (class "Default")
      (node (ref "M1") (pin "187") (pinfunction "ETH_LED1#_187") (pintype "passive+no_connect"))
    )
    (net (code "147") (name "unconnected-(M1B-ETH_LED2#-Pad189)") (class "Default")
      (node (ref "M1") (pin "189") (pinfunction "ETH_LED2#_189") (pintype "passive+no_connect"))
    )
    (net (code "148") (name "unconnected-(M1B-FLASH_CLK-Pad182)") (class "Default")
      (node (ref "M1") (pin "182") (pinfunction "FLASH_CLK_182") (pintype "passive+no_connect"))
    )
    (net (code "149") (name "unconnected-(M1B-FLASH_CS#-Pad188)") (class "Default")
      (node (ref "M1") (pin "188") (pinfunction "FLASH_CS#_188") (pintype "passive+no_connect"))
    )
    (net (code "150") (name "unconnected-(M1B-FLASH_DI-Pad186)") (class "Default")
      (node (ref "M1") (pin "186") (pinfunction "FLASH_DI_186") (pintype "passive+no_connect"))
    )
    (net (code "151") (name "unconnected-(M1B-FLASH_DO-Pad184)") (class "Default")
      (node (ref "M1") (pin "184") (pinfunction "FLASH_DO_184") (pintype "passive+no_connect"))
    )
    (net (code "152") (name "unconnected-(M1B-I2C_INT#-Pad174)") (class "Default")
      (node (ref "M1") (pin "174") (pinfunction "I2C_INT#_174") (pintype "passive+no_connect"))
    )
    (net (code "153") (name "unconnected-(M1B-IO_N-Pad111)") (class "Default")
      (node (ref "M1") (pin "111") (pinfunction "IO_N_111") (pintype "passive+no_connect"))
    )
    (net (code "154") (name "unconnected-(M1B-IO_P-Pad109)") (class "Default")
      (node (ref "M1") (pin "109") (pinfunction "IO_P_109") (pintype "passive+no_connect"))
    )
    (net (code "155") (name "unconnected-(M1B-RSVD-Pad168)") (class "Default")
      (node (ref "M1") (pin "168") (pinfunction "RSVD_168") (pintype "passive+no_connect"))
    )
    (net (code "156") (name "unconnected-(M1B-RSVD-Pad170)") (class "Default")
      (node (ref "M1") (pin "170") (pinfunction "RSVD_170") (pintype "passive+no_connect"))
    )
    (net (code "157") (name "unconnected-(M1B-SCLK_N-Pad105)") (class "Default")
      (node (ref "M1") (pin "105") (pinfunction "SCLK_N_105") (pintype "passive+no_connect"))
    )
    (net (code "158") (name "unconnected-(M1B-SCLK_P-Pad103)") (class "Default")
      (node (ref "M1") (pin "103") (pinfunction "SCLK_P_103") (pintype "passive+no_connect"))
    )
    (net (code "159") (name "unconnected-(M1B-USB_CPEN-Pad166)") (class "Default")
      (node (ref "M1") (pin "166") (pinfunction "USB_CPEN_166") (pintype "passive+no_connect"))
    )
    (net (code "160") (name "unconnected-(M1B-VMON-Pad198)") (class "Default")
      (node (ref "M1") (pin "198") (pinfunction "VMON_198") (pintype "passive"))
    )
    (net (code "161") (name "unconnected-(M1B-VOUT_1V8-Pad101)") (class "Default")
      (node (ref "M1") (pin "101") (pinfunction "VOUT_1V8_101") (pintype "passive+no_connect"))
    )
  )
)
